# SNR8503M_BLDC_SNLS_6-80V_20A_V2_0.net
KiCad netlist of a schematic drawn in Altium Designer
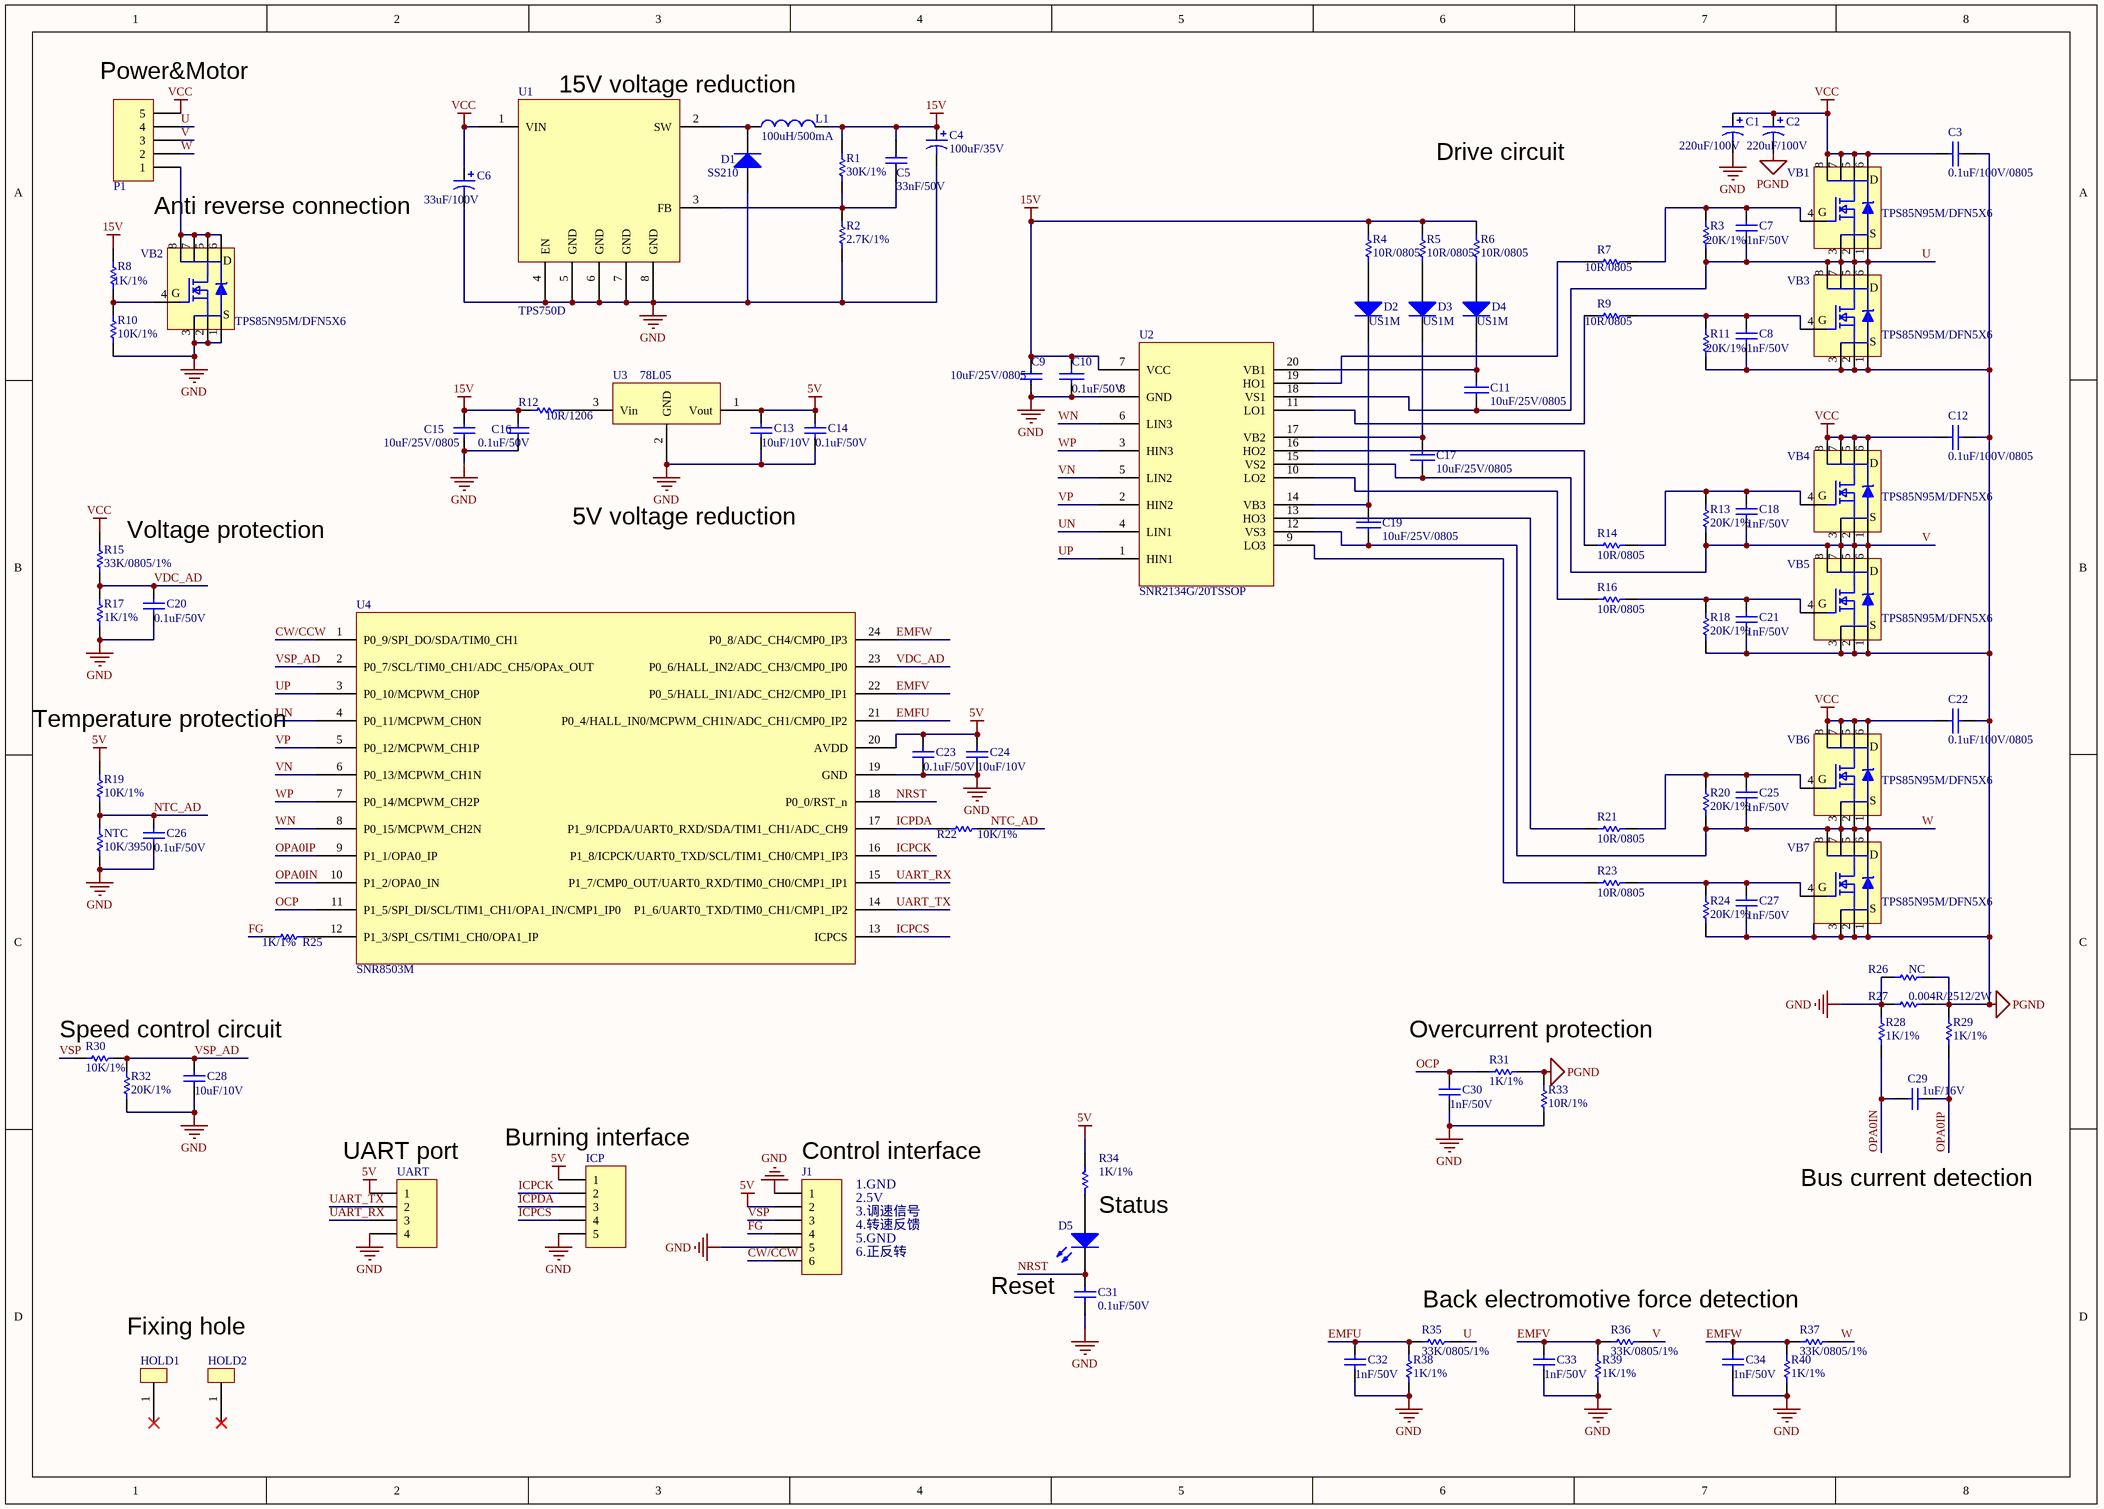
[diagram p0: SNR8503M_BLDC_SNLS_6-80V_20A_V2.0.SchDoc]

(export (version "E")
  (design (tool "Eeschema 10.0.6"))
  (components
    (comp (ref "C1")
      (value "220uF/100V")
      (footprint "CAP 5.0*12.5*20")
      (description "Polarized Capacitor (Radial)")
      (fields (field (name "PUBLISHER") "Altium Limited"))
      (libsource (lib "Miscellaneous Devices") (part "Cap Pol1"))
    )
    (comp (ref "C2")
      (value "220uF/100V")
      (footprint "CAP 5.0*12.5*20")
      (description "Polarized Capacitor (Radial)")
      (fields (field (name "PUBLISHER") "Altium Limited"))
      (libsource (lib "Miscellaneous Devices") (part "Cap Pol1"))
    )
    (comp (ref "C3")
      (value "0.1uF/100V/0805")
      (footprint "C 0805_L")
      (description "Capacitor")
      (libsource (lib "*") (part "C"))
    )
    (comp (ref "C4")
      (value "100uF/35V")
      (footprint "CM D(6.3*7.7)")
      (description "Polarized Capacitor (Radial)")
      (fields (field (name "PUBLISHER") "Altium Limited"))
      (libsource (lib "Miscellaneous Devices") (part "Cap Pol1"))
    )
    (comp (ref "C5")
      (value "33nF/50V")
      (footprint "C 0603_L")
      (description "Capacitor")
      (fields (field (name "PUBLISHER") "Altium Limited"))
      (libsource (lib "Miscellaneous Devices") (part "Cap"))
    )
    (comp (ref "C6")
      (value "33uF/100V")
      (footprint "CM F(10*10.2)")
      (description "Polarized Capacitor (Radial)")
      (fields (field (name "PUBLISHER") "Altium Limited"))
      (libsource (lib "Miscellaneous Devices") (part "Cap Pol1"))
    )
    (comp (ref "C7")
      (value "1nF/50V")
      (footprint "C 0603_L")
      (description "Capacitor")
      (fields (field (name "PUBLISHER") "Altium Limited"))
      (libsource (lib "Miscellaneous Devices") (part "Cap"))
    )
    (comp (ref "C8")
      (value "1nF/50V")
      (footprint "C 0603_L")
      (description "Capacitor")
      (fields (field (name "PUBLISHER") "Altium Limited"))
      (libsource (lib "Miscellaneous Devices") (part "Cap"))
    )
    (comp (ref "C9")
      (value "10uF/25V/0805")
      (footprint "C 0805_L")
      (description "Capacitor")
      (fields (field (name "PUBLISHER") "Altium Limited"))
      (libsource (lib "Miscellaneous Devices") (part "Cap"))
    )
    (comp (ref "C10")
      (value "0.1uF/50V")
      (footprint "C 0603_L")
      (description "Capacitor")
      (libsource (lib "*") (part "C"))
    )
    (comp (ref "C11")
      (value "10uF/25V/0805")
      (footprint "C 0805_L")
      (description "Capacitor")
      (libsource (lib "*") (part "C"))
    )
    (comp (ref "C12")
      (value "0.1uF/100V/0805")
      (footprint "C 0805_L")
      (description "Capacitor")
      (libsource (lib "*") (part "C"))
    )
    (comp (ref "C13")
      (value "10uF/10V")
      (footprint "C 0603_L")
      (description "Capacitor")
      (fields (field (name "PUBLISHER") "Altium Limited"))
      (libsource (lib "Miscellaneous Devices") (part "Cap"))
    )
    (comp (ref "C14")
      (value "0.1uF/50V")
      (footprint "C 0603_L")
      (description "Capacitor")
      (fields (field (name "PUBLISHER") "Altium Limited"))
      (libsource (lib "Miscellaneous Devices") (part "Cap"))
    )
    (comp (ref "C15")
      (value "10uF/25V/0805")
      (footprint "C 0805_L")
      (description "Capacitor")
      (fields (field (name "PUBLISHER") "Altium Limited"))
      (libsource (lib "Miscellaneous Devices") (part "Cap"))
    )
    (comp (ref "C16")
      (value "0.1uF/50V")
      (footprint "C 0603_L")
      (description "Capacitor")
      (fields (field (name "PUBLISHER") "Altium Limited"))
      (libsource (lib "Miscellaneous Devices") (part "Cap"))
    )
    (comp (ref "C17")
      (value "10uF/25V/0805")
      (footprint "C 0805_L")
      (description "Capacitor")
      (libsource (lib "*") (part "C"))
    )
    (comp (ref "C18")
      (value "1nF/50V")
      (footprint "C 0603_L")
      (description "Capacitor")
      (fields (field (name "PUBLISHER") "Altium Limited"))
      (libsource (lib "Miscellaneous Devices") (part "Cap"))
    )
    (comp (ref "C19")
      (value "10uF/25V/0805")
      (footprint "C 0805_L")
      (description "Capacitor")
      (libsource (lib "*") (part "C"))
    )
    (comp (ref "C20")
      (value "0.1uF/50V")
      (footprint "C 0603_L")
      (description "Capacitor")
      (fields (field (name "PUBLISHER") "Altium Limited"))
      (libsource (lib "Miscellaneous Devices") (part "Cap"))
    )
    (comp (ref "C21")
      (value "1nF/50V")
      (footprint "C 0603_L")
      (description "Capacitor")
      (fields (field (name "PUBLISHER") "Altium Limited"))
      (libsource (lib "Miscellaneous Devices") (part "Cap"))
    )
    (comp (ref "C22")
      (value "0.1uF/100V/0805")
      (footprint "C 0805_L")
      (description "Capacitor")
      (libsource (lib "*") (part "C"))
    )
    (comp (ref "C23")
      (value "0.1uF/50V")
      (footprint "C 0603_L")
      (description "Capacitor")
      (fields (field (name "PUBLISHER") "Altium Limited"))
      (libsource (lib "Miscellaneous Devices") (part "Cap"))
    )
    (comp (ref "C24")
      (value "10uF/10V")
      (footprint "C 0603_L")
      (description "Capacitor")
      (fields (field (name "PUBLISHER") "Altium Limited"))
      (libsource (lib "Miscellaneous Devices") (part "Cap"))
    )
    (comp (ref "C25")
      (value "1nF/50V")
      (footprint "C 0603_L")
      (description "Capacitor")
      (fields (field (name "PUBLISHER") "Altium Limited"))
      (libsource (lib "Miscellaneous Devices") (part "Cap"))
    )
    (comp (ref "C26")
      (value "0.1uF/50V")
      (footprint "C 0603_L")
      (description "Capacitor")
      (fields (field (name "PUBLISHER") "Altium Limited"))
      (libsource (lib "Miscellaneous Devices") (part "Cap"))
    )
    (comp (ref "C27")
      (value "1nF/50V")
      (footprint "C 0603_L")
      (description "Capacitor")
      (fields (field (name "PUBLISHER") "Altium Limited"))
      (libsource (lib "Miscellaneous Devices") (part "Cap"))
    )
    (comp (ref "C28")
      (value "10uF/10V")
      (footprint "C 0603_L")
      (description "Capacitor")
      (fields (field (name "PUBLISHER") "Altium Limited"))
      (libsource (lib "Miscellaneous Devices") (part "Cap"))
    )
    (comp (ref "C29")
      (value "1uF/16V")
      (footprint "C 0603_L")
      (description "Capacitor")
      (fields (field (name "PUBLISHER") "Altium Limited"))
      (libsource (lib "Miscellaneous Devices") (part "Cap"))
    )
    (comp (ref "C30")
      (value "1nF/50V")
      (footprint "C 0603_L")
      (description "Capacitor")
      (fields (field (name "PUBLISHER") "Altium Limited"))
      (libsource (lib "Miscellaneous Devices") (part "Cap"))
    )
    (comp (ref "C31")
      (value "0.1uF/50V")
      (footprint "C 0603_L")
      (description "Capacitor")
      (fields (field (name "PUBLISHER") "Altium Limited"))
      (libsource (lib "Miscellaneous Devices") (part "Cap"))
    )
    (comp (ref "C32")
      (value "1nF/50V")
      (footprint "C 0603_L")
      (description "Capacitor")
      (fields (field (name "PUBLISHER") "Altium Limited"))
      (libsource (lib "Miscellaneous Devices") (part "Cap"))
    )
    (comp (ref "C33")
      (value "1nF/50V")
      (footprint "C 0603_L")
      (description "Capacitor")
      (fields (field (name "PUBLISHER") "Altium Limited"))
      (libsource (lib "Miscellaneous Devices") (part "Cap"))
    )
    (comp (ref "C34")
      (value "1nF/50V")
      (footprint "C 0603_L")
      (description "Capacitor")
      (fields (field (name "PUBLISHER") "Altium Limited"))
      (libsource (lib "Miscellaneous Devices") (part "Cap"))
    )
    (comp (ref "D1")
      (value "SS210")
      (footprint "SMA")
      (description "Default Diode")
      (fields (field (name "PUBLISHER") "Altium Limited"))
      (libsource (lib "Miscellaneous Devices") (part "Diode"))
    )
    (comp (ref "D2")
      (value "US1M")
      (footprint "SOD-123")
      (description "Default Diode")
      (fields (field (name "PUBLISHER") "Altium Limited"))
      (libsource (lib "Miscellaneous Devices") (part "Diode"))
    )
    (comp (ref "D3")
      (value "US1M")
      (footprint "SOD-123")
      (description "Default Diode")
      (fields (field (name "PUBLISHER") "Altium Limited"))
      (libsource (lib "Miscellaneous Devices") (part "Diode"))
    )
    (comp (ref "D4")
      (value "US1M")
      (footprint "SOD-123")
      (description "Default Diode")
      (fields (field (name "PUBLISHER") "Altium Limited"))
      (libsource (lib "Miscellaneous Devices") (part "Diode"))
    )
    (comp (ref "D5")
      (value "LED0")
      (footprint "LED 0805R")
      (description "Typical INFRARED GaAs LED")
      (fields (field (name "PUBLISHER") "Altium Limited"))
      (libsource (lib "Miscellaneous Devices") (part "LED0"))
    )
    (comp (ref "HOLD1")
      (value "TEST POINT")
      (footprint "HOLD330-600")
      (libsource (lib "SNANER—SCH库") (part "TEST POINT"))
    )
    (comp (ref "HOLD2")
      (value "TEST POINT")
      (footprint "HOLD330-600")
      (libsource (lib "SNANER—SCH库") (part "TEST POINT"))
    )
    (comp (ref "ICP")
      (value "ICP")
      (footprint "HDR2.54-LI-5P")
      (description "Header, 5-Pin")
      (fields (field (name "PUBLISHER") "Altium Limited"))
      (libsource (lib "") (part "Header 5_1"))
    )
    (comp (ref "J1")
      (value "J1")
      (footprint "HDR2.54-LI-6P")
      (description "Header, 6-Pin")
      (fields (field (name "PUBLISHER") "Altium Limited"))
      (libsource (lib "Miscellaneous Connectors") (part "Header 6"))
    )
    (comp (ref "L1")
      (value "100uH/500mA")
      (footprint "NR5020")
      (description "Inductor")
      (fields (field (name "PUBLISHER") "Altium Limited"))
      (libsource (lib "Miscellaneous Devices") (part "Inductor"))
    )
    (comp (ref "NTC")
      (value "10K/3950")
      (footprint "R 0603_L")
      (description "Resistor")
      (fields (field (name "PUBLISHER") "Altium Limited"))
      (libsource (lib "Miscellaneous Devices") (part "Res1"))
    )
    (comp (ref "P1")
      (value "P1")
      (footprint "CONN-TH-5.08-5P")
      (description "Header, 5-Pin")
      (fields (field (name "PUBLISHER") "Altium Limited"))
      (libsource (lib "Miscellaneous Connectors") (part "Header 5"))
    )
    (comp (ref "R1")
      (value "30K/1%")
      (footprint "R 0603_L")
      (description "Resistor")
      (fields (field (name "PUBLISHER") "Altium Limited"))
      (libsource (lib "Miscellaneous Devices") (part "Res1"))
    )
    (comp (ref "R2")
      (value "2.7K/1%")
      (footprint "R 0603_L")
      (description "Resistor")
      (fields (field (name "PUBLISHER") "Altium Limited"))
      (libsource (lib "Miscellaneous Devices") (part "Res1"))
    )
    (comp (ref "R3")
      (value "20K/1%")
      (footprint "R 0603_L")
      (description "Resistor")
      (fields (field (name "PUBLISHER") "Altium Limited"))
      (libsource (lib "Miscellaneous Devices") (part "Res1"))
    )
    (comp (ref "R4")
      (value "10R/0805")
      (footprint "R 0805_L")
      (description "Resistor")
      (fields (field (name "PUBLISHER") "Altium Limited"))
      (libsource (lib "Miscellaneous Devices") (part "Res1"))
    )
    (comp (ref "R5")
      (value "10R/0805")
      (footprint "R 0805_L")
      (description "Resistor")
      (fields (field (name "PUBLISHER") "Altium Limited"))
      (libsource (lib "Miscellaneous Devices") (part "Res1"))
    )
    (comp (ref "R6")
      (value "10R/0805")
      (footprint "R 0805_L")
      (description "Resistor")
      (fields (field (name "PUBLISHER") "Altium Limited"))
      (libsource (lib "Miscellaneous Devices") (part "Res1"))
    )
    (comp (ref "R7")
      (value "10R/0805")
      (footprint "R 0805_L")
      (description "Resistor")
      (fields (field (name "PUBLISHER") "Altium Limited"))
      (libsource (lib "Miscellaneous Devices") (part "Res1"))
    )
    (comp (ref "R8")
      (value "1K/1%")
      (footprint "R 0603_L")
      (description "Resistor")
      (fields (field (name "PUBLISHER") "Altium Limited"))
      (libsource (lib "Miscellaneous Devices") (part "Res1"))
    )
    (comp (ref "R9")
      (value "10R/0805")
      (footprint "R 0805_L")
      (description "Resistor")
      (fields (field (name "PUBLISHER") "Altium Limited"))
      (libsource (lib "Miscellaneous Devices") (part "Res1"))
    )
    (comp (ref "R10")
      (value "10K/1%")
      (footprint "R 0603_L")
      (description "Resistor")
      (fields (field (name "PUBLISHER") "Altium Limited"))
      (libsource (lib "Miscellaneous Devices") (part "Res1"))
    )
    (comp (ref "R11")
      (value "20K/1%")
      (footprint "R 0603_L")
      (description "Resistor")
      (fields (field (name "PUBLISHER") "Altium Limited"))
      (libsource (lib "Miscellaneous Devices") (part "Res1"))
    )
    (comp (ref "R12")
      (value "10R/1206")
      (footprint "R 1206_L")
      (description "Resistor")
      (fields (field (name "PUBLISHER") "Altium Limited"))
      (libsource (lib "Miscellaneous Devices") (part "Res1"))
    )
    (comp (ref "R13")
      (value "20K/1%")
      (footprint "R 0603_L")
      (description "Resistor")
      (fields (field (name "PUBLISHER") "Altium Limited"))
      (libsource (lib "Miscellaneous Devices") (part "Res1"))
    )
    (comp (ref "R14")
      (value "10R/0805")
      (footprint "R 0805_L")
      (description "Resistor")
      (fields (field (name "PUBLISHER") "Altium Limited"))
      (libsource (lib "Miscellaneous Devices") (part "Res1"))
    )
    (comp (ref "R15")
      (value "33K/0805/1%")
      (footprint "R 0805_L")
      (description "Resistor")
      (fields (field (name "PUBLISHER") "Altium Limited"))
      (libsource (lib "Miscellaneous Devices") (part "Res1"))
    )
    (comp (ref "R16")
      (value "10R/0805")
      (footprint "R 0805_L")
      (description "Resistor")
      (fields (field (name "PUBLISHER") "Altium Limited"))
      (libsource (lib "Miscellaneous Devices") (part "Res1"))
    )
    (comp (ref "R17")
      (value "1K/1%")
      (footprint "R 0603_L")
      (description "Resistor")
      (fields (field (name "PUBLISHER") "Altium Limited"))
      (libsource (lib "Miscellaneous Devices") (part "Res1"))
    )
    (comp (ref "R18")
      (value "20K/1%")
      (footprint "R 0603_L")
      (description "Resistor")
      (fields (field (name "PUBLISHER") "Altium Limited"))
      (libsource (lib "Miscellaneous Devices") (part "Res1"))
    )
    (comp (ref "R19")
      (value "10K/1%")
      (footprint "R 0603_L")
      (description "Resistor")
      (fields (field (name "PUBLISHER") "Altium Limited"))
      (libsource (lib "Miscellaneous Devices") (part "Res1"))
    )
    (comp (ref "R20")
      (value "20K/1%")
      (footprint "R 0603_L")
      (description "Resistor")
      (fields (field (name "PUBLISHER") "Altium Limited"))
      (libsource (lib "Miscellaneous Devices") (part "Res1"))
    )
    (comp (ref "R21")
      (value "10R/0805")
      (footprint "R 0805_L")
      (description "Resistor")
      (fields (field (name "PUBLISHER") "Altium Limited"))
      (libsource (lib "Miscellaneous Devices") (part "Res1"))
    )
    (comp (ref "R22")
      (value "10K/1%")
      (footprint "R 0603_L")
      (description "Resistor")
      (fields (field (name "PUBLISHER") "Altium Limited"))
      (libsource (lib "Miscellaneous Devices") (part "Res1"))
    )
    (comp (ref "R23")
      (value "10R/0805")
      (footprint "R 0805_L")
      (description "Resistor")
      (fields (field (name "PUBLISHER") "Altium Limited"))
      (libsource (lib "Miscellaneous Devices") (part "Res1"))
    )
    (comp (ref "R24")
      (value "20K/1%")
      (footprint "R 0603_L")
      (description "Resistor")
      (fields (field (name "PUBLISHER") "Altium Limited"))
      (libsource (lib "Miscellaneous Devices") (part "Res1"))
    )
    (comp (ref "R25")
      (value "1K/1%")
      (footprint "R 0603_L")
      (description "Resistor")
      (fields (field (name "PUBLISHER") "Altium Limited"))
      (libsource (lib "Miscellaneous Devices") (part "Res1"))
    )
    (comp (ref "R26")
      (value "NC")
      (footprint "R 2512_L")
      (description "Resistor")
      (fields (field (name "PUBLISHER") "Altium Limited"))
      (libsource (lib "Miscellaneous Devices") (part "Res1"))
    )
    (comp (ref "R27")
      (value "0.004R/2512/2W")
      (footprint "R 2512_L")
      (description "Resistor")
      (fields (field (name "PUBLISHER") "Altium Limited"))
      (libsource (lib "Miscellaneous Devices") (part "Res1"))
    )
    (comp (ref "R28")
      (value "1K/1%")
      (footprint "R 0603_L")
      (description "Resistor")
      (fields (field (name "PUBLISHER") "Altium Limited"))
      (libsource (lib "Miscellaneous Devices") (part "Res1"))
    )
    (comp (ref "R29")
      (value "1K/1%")
      (footprint "R 0603_L")
      (description "Resistor")
      (fields (field (name "PUBLISHER") "Altium Limited"))
      (libsource (lib "Miscellaneous Devices") (part "Res1"))
    )
    (comp (ref "R30")
      (value "10K/1%")
      (footprint "R 0603_L")
      (description "Resistor")
      (fields (field (name "PUBLISHER") "Altium Limited"))
      (libsource (lib "Miscellaneous Devices") (part "Res1"))
    )
    (comp (ref "R31")
      (value "1K/1%")
      (footprint "R 0603_L")
      (description "Resistor")
      (fields (field (name "PUBLISHER") "Altium Limited"))
      (libsource (lib "Miscellaneous Devices") (part "Res1"))
    )
    (comp (ref "R32")
      (value "20K/1%")
      (footprint "R 0603_L")
      (description "Resistor")
      (fields (field (name "PUBLISHER") "Altium Limited"))
      (libsource (lib "Miscellaneous Devices") (part "Res1"))
    )
    (comp (ref "R33")
      (value "10R/1%")
      (footprint "R 0603_L")
      (description "Resistor")
      (fields (field (name "PUBLISHER") "Altium Limited"))
      (libsource (lib "Miscellaneous Devices") (part "Res1"))
    )
    (comp (ref "R34")
      (value "1K/1%")
      (footprint "R 0603_L")
      (description "Resistor")
      (fields (field (name "PUBLISHER") "Altium Limited"))
      (libsource (lib "Miscellaneous Devices") (part "Res1"))
    )
    (comp (ref "R35")
      (value "33K/0805/1%")
      (footprint "R 0805_L")
      (description "Resistor")
      (fields (field (name "PUBLISHER") "Altium Limited"))
      (libsource (lib "Miscellaneous Devices") (part "Res1"))
    )
    (comp (ref "R36")
      (value "33K/0805/1%")
      (footprint "R 0805_L")
      (description "Resistor")
      (fields (field (name "PUBLISHER") "Altium Limited"))
      (libsource (lib "Miscellaneous Devices") (part "Res1"))
    )
    (comp (ref "R37")
      (value "33K/0805/1%")
      (footprint "R 0805_L")
      (description "Resistor")
      (fields (field (name "PUBLISHER") "Altium Limited"))
      (libsource (lib "Miscellaneous Devices") (part "Res1"))
    )
    (comp (ref "R38")
      (value "1K/1%")
      (footprint "R 0603_L")
      (description "Resistor")
      (fields (field (name "PUBLISHER") "Altium Limited"))
      (libsource (lib "Miscellaneous Devices") (part "Res1"))
    )
    (comp (ref "R39")
      (value "1K/1%")
      (footprint "R 0603_L")
      (description "Resistor")
      (fields (field (name "PUBLISHER") "Altium Limited"))
      (libsource (lib "Miscellaneous Devices") (part "Res1"))
    )
    (comp (ref "R40")
      (value "1K/1%")
      (footprint "R 0603_L")
      (description "Resistor")
      (fields (field (name "PUBLISHER") "Altium Limited"))
      (libsource (lib "Miscellaneous Devices") (part "Res1"))
    )
    (comp (ref "U1")
      (value "TPS750D")
      (footprint "SOIC-8_EP")
      (libsource (lib "SNANER—SCH库") (part "TPS750D"))
    )
    (comp (ref "U2")
      (value "SNR2134G/20TSSOP")
      (footprint "TSSOP20_L")
      (libsource (lib "SNANER—SCH库") (part "SNR2134G"))
    )
    (comp (ref "U3") (value "78L05") (footprint "SOT89_L") (libsource (lib "SNANER—SCH库") (part "78L05")))
    (comp (ref "U4")
      (value "SNR8503M")
      (footprint "SSOP-24_150mil")
      (libsource (lib "SNANER—SCH库") (part "SNR8503M_1"))
    )
    (comp (ref "UART")
      (value "UART")
      (footprint "HDR2.54-LI-4P")
      (description "Header, 4-Pin")
      (fields (field (name "PUBLISHER") "Altium Limited"))
      (libsource (lib "Miscellaneous Connectors") (part "Header 4"))
    )
    (comp (ref "VB1")
      (value "TPS85N95M/DFN5X6")
      (footprint "DFN5x6-8L_TPS")
      (description "MOS")
      (libsource (lib "SNANER—SCH库") (part "MOSFET8-A"))
    )
    (comp (ref "VB2")
      (value "TPS85N95M/DFN5X6")
      (footprint "DFN5x6-8L_TPS")
      (description "MOS")
      (libsource (lib "SNANER—SCH库") (part "MOSFET8-A"))
    )
    (comp (ref "VB3")
      (value "TPS85N95M/DFN5X6")
      (footprint "DFN5x6-8L_TPS")
      (description "MOS")
      (libsource (lib "SNANER—SCH库") (part "MOSFET8-A"))
    )
    (comp (ref "VB4")
      (value "TPS85N95M/DFN5X6")
      (footprint "DFN5x6-8L_TPS")
      (description "MOS")
      (libsource (lib "SNANER—SCH库") (part "MOSFET8-A"))
    )
    (comp (ref "VB5")
      (value "TPS85N95M/DFN5X6")
      (footprint "DFN5x6-8L_TPS")
      (description "MOS")
      (libsource (lib "SNANER—SCH库") (part "MOSFET8-A"))
    )
    (comp (ref "VB6")
      (value "TPS85N95M/DFN5X6")
      (footprint "DFN5x6-8L_TPS")
      (description "MOS")
      (libsource (lib "SNANER—SCH库") (part "MOSFET8-A"))
    )
    (comp (ref "VB7")
      (value "TPS85N95M/DFN5X6")
      (footprint "DFN5x6-8L_TPS")
      (description "MOS")
      (libsource (lib "SNANER—SCH库") (part "MOSFET8-A"))
    )
  )
  (nets
    (net (code "7") (name "/CW{slash}CCW") (class "Default")
      (node (ref "J1") (pin "6") (pinfunction "6_6") (pintype "passive"))
      (node (ref "U4") (pin "1") (pinfunction "P0_9/SPI_DO/SDA/TIM0_CH1_1") (pintype "passive"))
    )
    (net (code "10") (name "/EMFU") (class "Default")
      (node (ref "C32") (pin "2") (pinfunction "2_2") (pintype "passive"))
      (node (ref "R35") (pin "2") (pinfunction "2_2") (pintype "passive"))
      (node (ref "R38") (pin "1") (pinfunction "1_1") (pintype "passive"))
      (node (ref "U4") (pin "21") (pinfunction "P0_4/HALL_IN0/MCPWM_CH1N/ADC_CH1/CMP0_IP2_21") (pintype "passive"))
    )
    (net (code "11") (name "/EMFV") (class "Default")
      (node (ref "C33") (pin "2") (pinfunction "2_2") (pintype "passive"))
      (node (ref "R36") (pin "2") (pinfunction "2_2") (pintype "passive"))
      (node (ref "R39") (pin "1") (pinfunction "1_1") (pintype "passive"))
      (node (ref "U4") (pin "22") (pinfunction "P0_5/HALL_IN1/ADC_CH2/CMP0_IP1_22") (pintype "passive"))
    )
    (net (code "12") (name "/EMFW") (class "Default")
      (node (ref "C34") (pin "2") (pinfunction "2_2") (pintype "passive"))
      (node (ref "R37") (pin "2") (pinfunction "2_2") (pintype "passive"))
      (node (ref "R40") (pin "1") (pinfunction "1_1") (pintype "passive"))
      (node (ref "U4") (pin "24") (pinfunction "P0_8/ADC_CH4/CMP0_IP3_24") (pintype "passive"))
    )
    (net (code "13") (name "/FG") (class "Default")
      (node (ref "J1") (pin "4") (pinfunction "4_4") (pintype "passive"))
      (node (ref "R25") (pin "2") (pinfunction "2_2") (pintype "passive"))
    )
    (net (code "15") (name "/ICPCK") (class "Default")
      (node (ref "ICP") (pin "2") (pinfunction "2_2") (pintype "passive"))
      (node (ref "U4") (pin "16") (pinfunction "P1_8/ICPCK/UART0_TXD/SCL/TIM1_CH0/CMP1_IP3_16") (pintype "passive"))
    )
    (net (code "16") (name "/ICPCS") (class "Default")
      (node (ref "ICP") (pin "4") (pinfunction "4_4") (pintype "passive"))
      (node (ref "U4") (pin "13") (pinfunction "ICPCS_13") (pintype "passive"))
    )
    (net (code "17") (name "/ICPDA") (class "Default")
      (node (ref "ICP") (pin "3") (pinfunction "3_3") (pintype "passive"))
      (node (ref "R22") (pin "2") (pinfunction "2_2") (pintype "passive"))
      (node (ref "U4") (pin "17") (pinfunction "P1_9/ICPDA/UART0_RXD/SDA/TIM1_CH1/ADC_CH9_17") (pintype "passive"))
    )
    (net (code "18") (name "/NRST") (class "Default")
      (node (ref "C31") (pin "2") (pinfunction "2_2") (pintype "passive"))
      (node (ref "D5") (pin "2") (pinfunction "K_2") (pintype "passive"))
      (node (ref "U4") (pin "18") (pinfunction "P0_0/RST_n_18") (pintype "passive"))
    )
    (net (code "19") (name "/NTC_AD") (class "Default")
      (node (ref "C26") (pin "2") (pinfunction "2_2") (pintype "passive"))
      (node (ref "NTC") (pin "2") (pinfunction "2_2") (pintype "passive"))
      (node (ref "R19") (pin "1") (pinfunction "1_1") (pintype "passive"))
      (node (ref "R22") (pin "1") (pinfunction "1_1") (pintype "passive"))
    )
    (net (code "20") (name "/OCP") (class "Default")
      (node (ref "C30") (pin "2") (pinfunction "2_2") (pintype "passive"))
      (node (ref "R31") (pin "1") (pinfunction "1_1") (pintype "passive"))
      (node (ref "U4") (pin "11") (pinfunction "P1_5/SPI_DI/SCL/TIM1_CH1/OPA1_IN/CMP1_IP0_11") (pintype "passive"))
    )
    (net (code "21") (name "/OPA0IN") (class "Default")
      (node (ref "C29") (pin "2") (pinfunction "2_2") (pintype "passive"))
      (node (ref "R28") (pin "2") (pinfunction "2_2") (pintype "passive"))
      (node (ref "U4") (pin "10") (pinfunction "P1_2/OPA0_IN_10") (pintype "passive"))
    )
    (net (code "22") (name "/OPA0IP") (class "Default")
      (node (ref "C29") (pin "1") (pinfunction "1_1") (pintype "passive"))
      (node (ref "R29") (pin "2") (pinfunction "2_2") (pintype "passive"))
      (node (ref "U4") (pin "9") (pinfunction "P1_1/OPA0_IP_9") (pintype "passive"))
    )
    (net (code "29") (name "/U") (class "Default")
      (node (ref "C11") (pin "2") (pinfunction "2_2") (pintype "passive"))
      (node (ref "C7") (pin "1") (pinfunction "1_1") (pintype "passive"))
      (node (ref "P1") (pin "4") (pinfunction "4_4") (pintype "passive"))
      (node (ref "R3") (pin "2") (pinfunction "2_2") (pintype "passive"))
      (node (ref "R35") (pin "1") (pinfunction "1_1") (pintype "passive"))
      (node (ref "U2") (pin "18") (pinfunction "VS1_18") (pintype "passive"))
      (node (ref "VB1") (pin "1") (pinfunction "S_1") (pintype "passive"))
      (node (ref "VB1") (pin "2") (pinfunction "S_2") (pintype "passive"))
      (node (ref "VB1") (pin "3") (pinfunction "S_3") (pintype "passive"))
      (node (ref "VB3") (pin "5") (pinfunction "D_5") (pintype "passive"))
      (node (ref "VB3") (pin "6") (pinfunction "D_6") (pintype "passive"))
      (node (ref "VB3") (pin "7") (pinfunction "D_7") (pintype "passive"))
      (node (ref "VB3") (pin "8") (pinfunction "D_8") (pintype "passive"))
    )
    (net (code "31") (name "/UART_RX") (class "Default")
      (node (ref "U4") (pin "15") (pinfunction "P1_7/CMP0_OUT/UART0_RXD/TIM0_CH0/CMP1_IP1_15") (pintype "passive"))
      (node (ref "UART") (pin "3") (pinfunction "3_3") (pintype "passive"))
    )
    (net (code "32") (name "/UART_TX") (class "Default")
      (node (ref "U4") (pin "14") (pinfunction "P1_6/UART0_TXD/TIM0_CH1/CMP1_IP2_14") (pintype "passive"))
      (node (ref "UART") (pin "2") (pinfunction "2_2") (pintype "passive"))
    )
    (net (code "33") (name "/UN") (class "Default")
      (node (ref "U2") (pin "4") (pinfunction "LIN1_4") (pintype "passive"))
      (node (ref "U4") (pin "4") (pinfunction "P0_11/MCPWM_CH0N_4") (pintype "passive"))
    )
    (net (code "34") (name "/UP") (class "Default")
      (node (ref "U2") (pin "1") (pinfunction "HIN1_1") (pintype "passive"))
      (node (ref "U4") (pin "3") (pinfunction "P0_10/MCPWM_CH0P_3") (pintype "passive"))
    )
    (net (code "35") (name "/V") (class "Default")
      (node (ref "C17") (pin "2") (pinfunction "2_2") (pintype "passive"))
      (node (ref "C18") (pin "1") (pinfunction "1_1") (pintype "passive"))
      (node (ref "P1") (pin "3") (pinfunction "3_3") (pintype "passive"))
      (node (ref "R13") (pin "2") (pinfunction "2_2") (pintype "passive"))
      (node (ref "R36") (pin "1") (pinfunction "1_1") (pintype "passive"))
      (node (ref "U2") (pin "15") (pinfunction "VS2_15") (pintype "passive"))
      (node (ref "VB4") (pin "1") (pinfunction "S_1") (pintype "passive"))
      (node (ref "VB4") (pin "2") (pinfunction "S_2") (pintype "passive"))
      (node (ref "VB4") (pin "3") (pinfunction "S_3") (pintype "passive"))
      (node (ref "VB5") (pin "5") (pinfunction "D_5") (pintype "passive"))
      (node (ref "VB5") (pin "6") (pinfunction "D_6") (pintype "passive"))
      (node (ref "VB5") (pin "7") (pinfunction "D_7") (pintype "passive"))
      (node (ref "VB5") (pin "8") (pinfunction "D_8") (pintype "passive"))
    )
    (net (code "36") (name "/VDC_AD") (class "Default")
      (node (ref "C20") (pin "2") (pinfunction "2_2") (pintype "passive"))
      (node (ref "R15") (pin "1") (pinfunction "1_1") (pintype "passive"))
      (node (ref "R17") (pin "2") (pinfunction "2_2") (pintype "passive"))
      (node (ref "U4") (pin "23") (pinfunction "P0_6/HALL_IN2/ADC_CH3/CMP0_IP0_23") (pintype "passive"))
    )
    (net (code "37") (name "/VN") (class "Default")
      (node (ref "U2") (pin "5") (pinfunction "LIN2_5") (pintype "passive"))
      (node (ref "U4") (pin "6") (pinfunction "P0_13/MCPWM_CH1N_6") (pintype "passive"))
    )
    (net (code "38") (name "/VP") (class "Default")
      (node (ref "U2") (pin "2") (pinfunction "HIN2_2") (pintype "passive"))
      (node (ref "U4") (pin "5") (pinfunction "P0_12/MCPWM_CH1P_5") (pintype "passive"))
    )
    (net (code "39") (name "/VSP") (class "Default")
      (node (ref "J1") (pin "3") (pinfunction "3_3") (pintype "passive"))
      (node (ref "R30") (pin "2") (pinfunction "2_2") (pintype "passive"))
    )
    (net (code "40") (name "/VSP_AD") (class "Default")
      (node (ref "C28") (pin "2") (pinfunction "2_2") (pintype "passive"))
      (node (ref "R30") (pin "1") (pinfunction "1_1") (pintype "passive"))
      (node (ref "R32") (pin "1") (pinfunction "1_1") (pintype "passive"))
      (node (ref "U4") (pin "2") (pinfunction "P0_7/SCL/TIM0_CH1/ADC_CH5/OPAx_OUT_2") (pintype "passive"))
    )
    (net (code "42") (name "/W") (class "Default")
      (node (ref "C19") (pin "2") (pinfunction "2_2") (pintype "passive"))
      (node (ref "C25") (pin "1") (pinfunction "1_1") (pintype "passive"))
      (node (ref "P1") (pin "2") (pinfunction "2_2") (pintype "passive"))
      (node (ref "R20") (pin "2") (pinfunction "2_2") (pintype "passive"))
      (node (ref "R37") (pin "1") (pinfunction "1_1") (pintype "passive"))
      (node (ref "U2") (pin "12") (pinfunction "VS3_12") (pintype "passive"))
      (node (ref "VB6") (pin "1") (pinfunction "S_1") (pintype "passive"))
      (node (ref "VB6") (pin "2") (pinfunction "S_2") (pintype "passive"))
      (node (ref "VB6") (pin "3") (pinfunction "S_3") (pintype "passive"))
      (node (ref "VB7") (pin "5") (pinfunction "D_5") (pintype "passive"))
      (node (ref "VB7") (pin "6") (pinfunction "D_6") (pintype "passive"))
      (node (ref "VB7") (pin "7") (pinfunction "D_7") (pintype "passive"))
      (node (ref "VB7") (pin "8") (pinfunction "D_8") (pintype "passive"))
    )
    (net (code "43") (name "/WN") (class "Default")
      (node (ref "U2") (pin "6") (pinfunction "LIN3_6") (pintype "passive"))
      (node (ref "U4") (pin "8") (pinfunction "P0_15/MCPWM_CH2N_8") (pintype "passive"))
    )
    (net (code "44") (name "/WP") (class "Default")
      (node (ref "U2") (pin "3") (pinfunction "HIN3_3") (pintype "passive"))
      (node (ref "U4") (pin "7") (pinfunction "P0_14/MCPWM_CH2P_7") (pintype "passive"))
    )
    (net (code "45") (name "5V") (class "Default")
      (node (ref "C13") (pin "2") (pinfunction "2_2") (pintype "passive"))
      (node (ref "C14") (pin "2") (pinfunction "2_2") (pintype "passive"))
      (node (ref "C23") (pin "2") (pinfunction "2_2") (pintype "passive"))
      (node (ref "C24") (pin "2") (pinfunction "2_2") (pintype "passive"))
      (node (ref "ICP") (pin "1") (pinfunction "1_1") (pintype "passive"))
      (node (ref "J1") (pin "2") (pinfunction "2_2") (pintype "passive"))
      (node (ref "R19") (pin "2") (pinfunction "2_2") (pintype "passive"))
      (node (ref "R34") (pin "2") (pinfunction "2_2") (pintype "passive"))
      (node (ref "U3") (pin "1") (pinfunction "Vout_1") (pintype "passive"))
      (node (ref "U4") (pin "20") (pinfunction "AVDD_20") (pintype "passive"))
      (node (ref "UART") (pin "1") (pinfunction "1_1") (pintype "passive"))
    )
    (net (code "46") (name "15V") (class "Default")
      (node (ref "C10") (pin "2") (pinfunction "2_2") (pintype "passive"))
      (node (ref "C15") (pin "2") (pinfunction "2_2") (pintype "passive"))
      (node (ref "C16") (pin "2") (pinfunction "2_2") (pintype "passive"))
      (node (ref "C4") (pin "1") (pinfunction "1_1") (pintype "passive"))
      (node (ref "C5") (pin "2") (pinfunction "2_2") (pintype "passive"))
      (node (ref "C9") (pin "2") (pinfunction "2_2") (pintype "passive"))
      (node (ref "L1") (pin "2") (pinfunction "2_2") (pintype "passive"))
      (node (ref "R1") (pin "1") (pinfunction "1_1") (pintype "passive"))
      (node (ref "R12") (pin "2") (pinfunction "2_2") (pintype "passive"))
      (node (ref "R4") (pin "1") (pinfunction "1_1") (pintype "passive"))
      (node (ref "R5") (pin "1") (pinfunction "1_1") (pintype "passive"))
      (node (ref "R6") (pin "1") (pinfunction "1_1") (pintype "passive"))
      (node (ref "R8") (pin "2") (pinfunction "2_2") (pintype "passive"))
      (node (ref "U2") (pin "7") (pinfunction "VCC_7") (pintype "passive"))
    )
    (net (code "47") (name "GND") (class "Default")
      (node (ref "C1") (pin "2") (pinfunction "2_2") (pintype "passive"))
      (node (ref "C10") (pin "1") (pinfunction "1_1") (pintype "passive"))
      (node (ref "C13") (pin "1") (pinfunction "1_1") (pintype "passive"))
      (node (ref "C14") (pin "1") (pinfunction "1_1") (pintype "passive"))
      (node (ref "C15") (pin "1") (pinfunction "1_1") (pintype "passive"))
      (node (ref "C16") (pin "1") (pinfunction "1_1") (pintype "passive"))
      (node (ref "C20") (pin "1") (pinfunction "1_1") (pintype "passive"))
      (node (ref "C23") (pin "1") (pinfunction "1_1") (pintype "passive"))
      (node (ref "C24") (pin "1") (pinfunction "1_1") (pintype "passive"))
      (node (ref "C26") (pin "1") (pinfunction "1_1") (pintype "passive"))
      (node (ref "C28") (pin "1") (pinfunction "1_1") (pintype "passive"))
      (node (ref "C30") (pin "1") (pinfunction "1_1") (pintype "passive"))
      (node (ref "C31") (pin "1") (pinfunction "1_1") (pintype "passive"))
      (node (ref "C32") (pin "1") (pinfunction "1_1") (pintype "passive"))
      (node (ref "C33") (pin "1") (pinfunction "1_1") (pintype "passive"))
      (node (ref "C34") (pin "1") (pinfunction "1_1") (pintype "passive"))
      (node (ref "C4") (pin "2") (pinfunction "2_2") (pintype "passive"))
      (node (ref "C6") (pin "2") (pinfunction "2_2") (pintype "passive"))
      (node (ref "C9") (pin "1") (pinfunction "1_1") (pintype "passive"))
      (node (ref "D1") (pin "1") (pinfunction "A_1") (pintype "passive"))
      (node (ref "ICP") (pin "5") (pinfunction "5_5") (pintype "passive"))
      (node (ref "J1") (pin "1") (pinfunction "1_1") (pintype "passive"))
      (node (ref "J1") (pin "5") (pinfunction "5_5") (pintype "passive"))
      (node (ref "NTC") (pin "1") (pinfunction "1_1") (pintype "passive"))
      (node (ref "R10") (pin "1") (pinfunction "1_1") (pintype "passive"))
      (node (ref "R17") (pin "1") (pinfunction "1_1") (pintype "passive"))
      (node (ref "R2") (pin "2") (pinfunction "2_2") (pintype "passive"))
      (node (ref "R26") (pin "1") (pinfunction "1_1") (pintype "passive"))
      (node (ref "R27") (pin "1") (pinfunction "1_1") (pintype "passive"))
      (node (ref "R28") (pin "1") (pinfunction "1_1") (pintype "passive"))
      (node (ref "R32") (pin "2") (pinfunction "2_2") (pintype "passive"))
      (node (ref "R33") (pin "2") (pinfunction "2_2") (pintype "passive"))
      (node (ref "R38") (pin "2") (pinfunction "2_2") (pintype "passive"))
      (node (ref "R39") (pin "2") (pinfunction "2_2") (pintype "passive"))
      (node (ref "R40") (pin "2") (pinfunction "2_2") (pintype "passive"))
      (node (ref "U1") (pin "4") (pinfunction "EN_4") (pintype "passive"))
      (node (ref "U1") (pin "5") (pinfunction "GND_5") (pintype "passive"))
      (node (ref "U1") (pin "6") (pinfunction "GND_6") (pintype "passive"))
      (node (ref "U1") (pin "7") (pinfunction "GND_7") (pintype "passive"))
      (node (ref "U1") (pin "8") (pinfunction "GND_8") (pintype "passive"))
      (node (ref "U2") (pin "8") (pinfunction "GND_8") (pintype "passive"))
      (node (ref "U3") (pin "2") (pinfunction "GND_2") (pintype "passive"))
      (node (ref "U4") (pin "19") (pinfunction "GND_19") (pintype "passive"))
      (node (ref "UART") (pin "4") (pinfunction "4_4") (pintype "passive"))
      (node (ref "VB2") (pin "1") (pinfunction "S_1") (pintype "passive"))
      (node (ref "VB2") (pin "2") (pinfunction "S_2") (pintype "passive"))
      (node (ref "VB2") (pin "3") (pinfunction "S_3") (pintype "passive"))
    )
    (net (code "48") (name "Net-(D1-K)") (class "Default")
      (node (ref "D1") (pin "2") (pinfunction "K_2") (pintype "passive"))
      (node (ref "L1") (pin "1") (pinfunction "1_1") (pintype "passive"))
      (node (ref "U1") (pin "2") (pinfunction "SW_2") (pintype "passive"))
    )
    (net (code "49") (name "Net-(D2-A)") (class "Default")
      (node (ref "D2") (pin "1") (pinfunction "A_1") (pintype "passive"))
      (node (ref "R4") (pin "2") (pinfunction "2_2") (pintype "passive"))
    )
    (net (code "50") (name "Net-(D2-K)") (class "Default")
      (node (ref "C19") (pin "1") (pinfunction "1_1") (pintype "passive"))
      (node (ref "D2") (pin "2") (pinfunction "K_2") (pintype "passive"))
      (node (ref "U2") (pin "14") (pinfunction "VB3_14") (pintype "passive"))
    )
    (net (code "51") (name "Net-(D3-A)") (class "Default")
      (node (ref "D3") (pin "1") (pinfunction "A_1") (pintype "passive"))
      (node (ref "R5") (pin "2") (pinfunction "2_2") (pintype "passive"))
    )
    (net (code "52") (name "Net-(D3-K)") (class "Default")
      (node (ref "C17") (pin "1") (pinfunction "1_1") (pintype "passive"))
      (node (ref "D3") (pin "2") (pinfunction "K_2") (pintype "passive"))
      (node (ref "U2") (pin "17") (pinfunction "VB2_17") (pintype "passive"))
    )
    (net (code "53") (name "Net-(D4-A)") (class "Default")
      (node (ref "D4") (pin "1") (pinfunction "A_1") (pintype "passive"))
      (node (ref "R6") (pin "2") (pinfunction "2_2") (pintype "passive"))
    )
    (net (code "54") (name "Net-(D4-K)") (class "Default")
      (node (ref "C11") (pin "1") (pinfunction "1_1") (pintype "passive"))
      (node (ref "D4") (pin "2") (pinfunction "K_2") (pintype "passive"))
      (node (ref "U2") (pin "20") (pinfunction "VB1_20") (pintype "passive"))
    )
    (net (code "55") (name "Net-(D5-A)") (class "Default")
      (node (ref "D5") (pin "1") (pinfunction "A_1") (pintype "passive"))
      (node (ref "R34") (pin "1") (pinfunction "1_1") (pintype "passive"))
    )
    (net (code "56") (name "Net-(P1-Pad1)") (class "Default")
      (node (ref "P1") (pin "1") (pinfunction "1_1") (pintype "passive"))
      (node (ref "VB2") (pin "5") (pinfunction "D_5") (pintype "passive"))
      (node (ref "VB2") (pin "6") (pinfunction "D_6") (pintype "passive"))
      (node (ref "VB2") (pin "7") (pinfunction "D_7") (pintype "passive"))
      (node (ref "VB2") (pin "8") (pinfunction "D_8") (pintype "passive"))
    )
    (net (code "57") (name "Net-(U1-FB)") (class "Default")
      (node (ref "C5") (pin "1") (pinfunction "1_1") (pintype "passive"))
      (node (ref "R1") (pin "2") (pinfunction "2_2") (pintype "passive"))
      (node (ref "R2") (pin "1") (pinfunction "1_1") (pintype "passive"))
      (node (ref "U1") (pin "3") (pinfunction "FB_3") (pintype "passive"))
    )
    (net (code "58") (name "Net-(U2-HO1)") (class "Default")
      (node (ref "R7") (pin "2") (pinfunction "2_2") (pintype "passive"))
      (node (ref "U2") (pin "19") (pinfunction "HO1_19") (pintype "passive"))
    )
    (net (code "59") (name "Net-(U2-HO2)") (class "Default")
      (node (ref "R14") (pin "2") (pinfunction "2_2") (pintype "passive"))
      (node (ref "U2") (pin "16") (pinfunction "HO2_16") (pintype "passive"))
    )
    (net (code "60") (name "Net-(U2-HO3)") (class "Default")
      (node (ref "R21") (pin "2") (pinfunction "2_2") (pintype "passive"))
      (node (ref "U2") (pin "13") (pinfunction "HO3_13") (pintype "passive"))
    )
    (net (code "61") (name "Net-(U2-LO1)") (class "Default")
      (node (ref "R9") (pin "2") (pinfunction "2_2") (pintype "passive"))
      (node (ref "U2") (pin "11") (pinfunction "LO1_11") (pintype "passive"))
    )
    (net (code "62") (name "Net-(U2-LO2)") (class "Default")
      (node (ref "R16") (pin "2") (pinfunction "2_2") (pintype "passive"))
      (node (ref "U2") (pin "10") (pinfunction "LO2_10") (pintype "passive"))
    )
    (net (code "63") (name "Net-(U2-LO3)") (class "Default")
      (node (ref "R23") (pin "2") (pinfunction "2_2") (pintype "passive"))
      (node (ref "U2") (pin "9") (pinfunction "LO3_9") (pintype "passive"))
    )
    (net (code "64") (name "Net-(U3-Vin)") (class "Default")
      (node (ref "R12") (pin "1") (pinfunction "1_1") (pintype "passive"))
      (node (ref "U3") (pin "3") (pinfunction "Vin_3") (pintype "passive"))
    )
    (net (code "65") (name "Net-(U4-P1_3{slash}SPI_CS{slash}TIM1_CH0{slash}OPA1_IP)") (class "Default")
      (node (ref "R25") (pin "1") (pinfunction "1_1") (pintype "passive"))
      (node (ref "U4") (pin "12") (pinfunction "P1_3/SPI_CS/TIM1_CH0/OPA1_IP_12") (pintype "passive"))
    )
    (net (code "66") (name "Net-(VB1-G)") (class "Default")
      (node (ref "C7") (pin "2") (pinfunction "2_2") (pintype "passive"))
      (node (ref "R3") (pin "1") (pinfunction "1_1") (pintype "passive"))
      (node (ref "R7") (pin "1") (pinfunction "1_1") (pintype "passive"))
      (node (ref "VB1") (pin "4") (pinfunction "G_4") (pintype "passive"))
    )
    (net (code "67") (name "Net-(VB2-G)") (class "Default")
      (node (ref "R10") (pin "2") (pinfunction "2_2") (pintype "passive"))
      (node (ref "R8") (pin "1") (pinfunction "1_1") (pintype "passive"))
      (node (ref "VB2") (pin "4") (pinfunction "G_4") (pintype "passive"))
    )
    (net (code "68") (name "Net-(VB3-G)") (class "Default")
      (node (ref "C8") (pin "2") (pinfunction "2_2") (pintype "passive"))
      (node (ref "R11") (pin "1") (pinfunction "1_1") (pintype "passive"))
      (node (ref "R9") (pin "1") (pinfunction "1_1") (pintype "passive"))
      (node (ref "VB3") (pin "4") (pinfunction "G_4") (pintype "passive"))
    )
    (net (code "69") (name "Net-(VB4-G)") (class "Default")
      (node (ref "C18") (pin "2") (pinfunction "2_2") (pintype "passive"))
      (node (ref "R13") (pin "1") (pinfunction "1_1") (pintype "passive"))
      (node (ref "R14") (pin "1") (pinfunction "1_1") (pintype "passive"))
      (node (ref "VB4") (pin "4") (pinfunction "G_4") (pintype "passive"))
    )
    (net (code "70") (name "Net-(VB5-G)") (class "Default")
      (node (ref "C21") (pin "2") (pinfunction "2_2") (pintype "passive"))
      (node (ref "R16") (pin "1") (pinfunction "1_1") (pintype "passive"))
      (node (ref "R18") (pin "1") (pinfunction "1_1") (pintype "passive"))
      (node (ref "VB5") (pin "4") (pinfunction "G_4") (pintype "passive"))
    )
    (net (code "71") (name "Net-(VB6-G)") (class "Default")
      (node (ref "C25") (pin "2") (pinfunction "2_2") (pintype "passive"))
      (node (ref "R20") (pin "1") (pinfunction "1_1") (pintype "passive"))
      (node (ref "R21") (pin "1") (pinfunction "1_1") (pintype "passive"))
      (node (ref "VB6") (pin "4") (pinfunction "G_4") (pintype "passive"))
    )
    (net (code "72") (name "Net-(VB7-G)") (class "Default")
      (node (ref "C27") (pin "2") (pinfunction "2_2") (pintype "passive"))
      (node (ref "R23") (pin "1") (pinfunction "1_1") (pintype "passive"))
      (node (ref "R24") (pin "1") (pinfunction "1_1") (pintype "passive"))
      (node (ref "VB7") (pin "4") (pinfunction "G_4") (pintype "passive"))
    )
    (net (code "73") (name "PGND") (class "Default")
      (node (ref "C12") (pin "1") (pinfunction "1_1") (pintype "passive"))
      (node (ref "C2") (pin "2") (pinfunction "2_2") (pintype "passive"))
      (node (ref "C21") (pin "1") (pinfunction "1_1") (pintype "passive"))
      (node (ref "C22") (pin "1") (pinfunction "1_1") (pintype "passive"))
      (node (ref "C27") (pin "1") (pinfunction "1_1") (pintype "passive"))
      (node (ref "C3") (pin "1") (pinfunction "1_1") (pintype "passive"))
      (node (ref "C8") (pin "1") (pinfunction "1_1") (pintype "passive"))
      (node (ref "R11") (pin "2") (pinfunction "2_2") (pintype "passive"))
      (node (ref "R18") (pin "2") (pinfunction "2_2") (pintype "passive"))
      (node (ref "R24") (pin "2") (pinfunction "2_2") (pintype "passive"))
      (node (ref "R26") (pin "2") (pinfunction "2_2") (pintype "passive"))
      (node (ref "R27") (pin "2") (pinfunction "2_2") (pintype "passive"))
      (node (ref "R29") (pin "1") (pinfunction "1_1") (pintype "passive"))
      (node (ref "R31") (pin "2") (pinfunction "2_2") (pintype "passive"))
      (node (ref "R33") (pin "1") (pinfunction "1_1") (pintype "passive"))
      (node (ref "VB3") (pin "1") (pinfunction "S_1") (pintype "passive"))
      (node (ref "VB3") (pin "2") (pinfunction "S_2") (pintype "passive"))
      (node (ref "VB3") (pin "3") (pinfunction "S_3") (pintype "passive"))
      (node (ref "VB5") (pin "1") (pinfunction "S_1") (pintype "passive"))
      (node (ref "VB5") (pin "2") (pinfunction "S_2") (pintype "passive"))
      (node (ref "VB5") (pin "3") (pinfunction "S_3") (pintype "passive"))
      (node (ref "VB7") (pin "1") (pinfunction "S_1") (pintype "passive"))
      (node (ref "VB7") (pin "2") (pinfunction "S_2") (pintype "passive"))
      (node (ref "VB7") (pin "3") (pinfunction "S_3") (pintype "passive"))
    )
    (net (code "74") (name "VCC") (class "Default")
      (node (ref "C1") (pin "1") (pinfunction "1_1") (pintype "passive"))
      (node (ref "C12") (pin "2") (pinfunction "2_2") (pintype "passive"))
      (node (ref "C2") (pin "1") (pinfunction "1_1") (pintype "passive"))
      (node (ref "C22") (pin "2") (pinfunction "2_2") (pintype "passive"))
      (node (ref "C3") (pin "2") (pinfunction "2_2") (pintype "passive"))
      (node (ref "C6") (pin "1") (pinfunction "1_1") (pintype "passive"))
      (node (ref "P1") (pin "5") (pinfunction "5_5") (pintype "passive"))
      (node (ref "R15") (pin "2") (pinfunction "2_2") (pintype "passive"))
      (node (ref "U1") (pin "1") (pinfunction "VIN_1") (pintype "passive"))
      (node (ref "VB1") (pin "5") (pinfunction "D_5") (pintype "passive"))
      (node (ref "VB1") (pin "6") (pinfunction "D_6") (pintype "passive"))
      (node (ref "VB1") (pin "7") (pinfunction "D_7") (pintype "passive"))
      (node (ref "VB1") (pin "8") (pinfunction "D_8") (pintype "passive"))
      (node (ref "VB4") (pin "5") (pinfunction "D_5") (pintype "passive"))
      (node (ref "VB4") (pin "6") (pinfunction "D_6") (pintype "passive"))
      (node (ref "VB4") (pin "7") (pinfunction "D_7") (pintype "passive"))
      (node (ref "VB4") (pin "8") (pinfunction "D_8") (pintype "passive"))
      (node (ref "VB6") (pin "5") (pinfunction "D_5") (pintype "passive"))
      (node (ref "VB6") (pin "6") (pinfunction "D_6") (pintype "passive"))
      (node (ref "VB6") (pin "7") (pinfunction "D_7") (pintype "passive"))
      (node (ref "VB6") (pin "8") (pinfunction "D_8") (pintype "passive"))
    )
    (net (code "75") (name "unconnected-(HOLD1-VOUT-Pad1)") (class "Default")
      (node (ref "HOLD1") (pin "1") (pinfunction "VOUT_1") (pintype "passive+no_connect"))
    )
    (net (code "76") (name "unconnected-(HOLD2-VOUT-Pad1)") (class "Default")
      (node (ref "HOLD2") (pin "1") (pinfunction "VOUT_1") (pintype "passive+no_connect"))
    )
  )
)
